# dsc.net
KiCad netlist of a schematic drawn in EAGLE
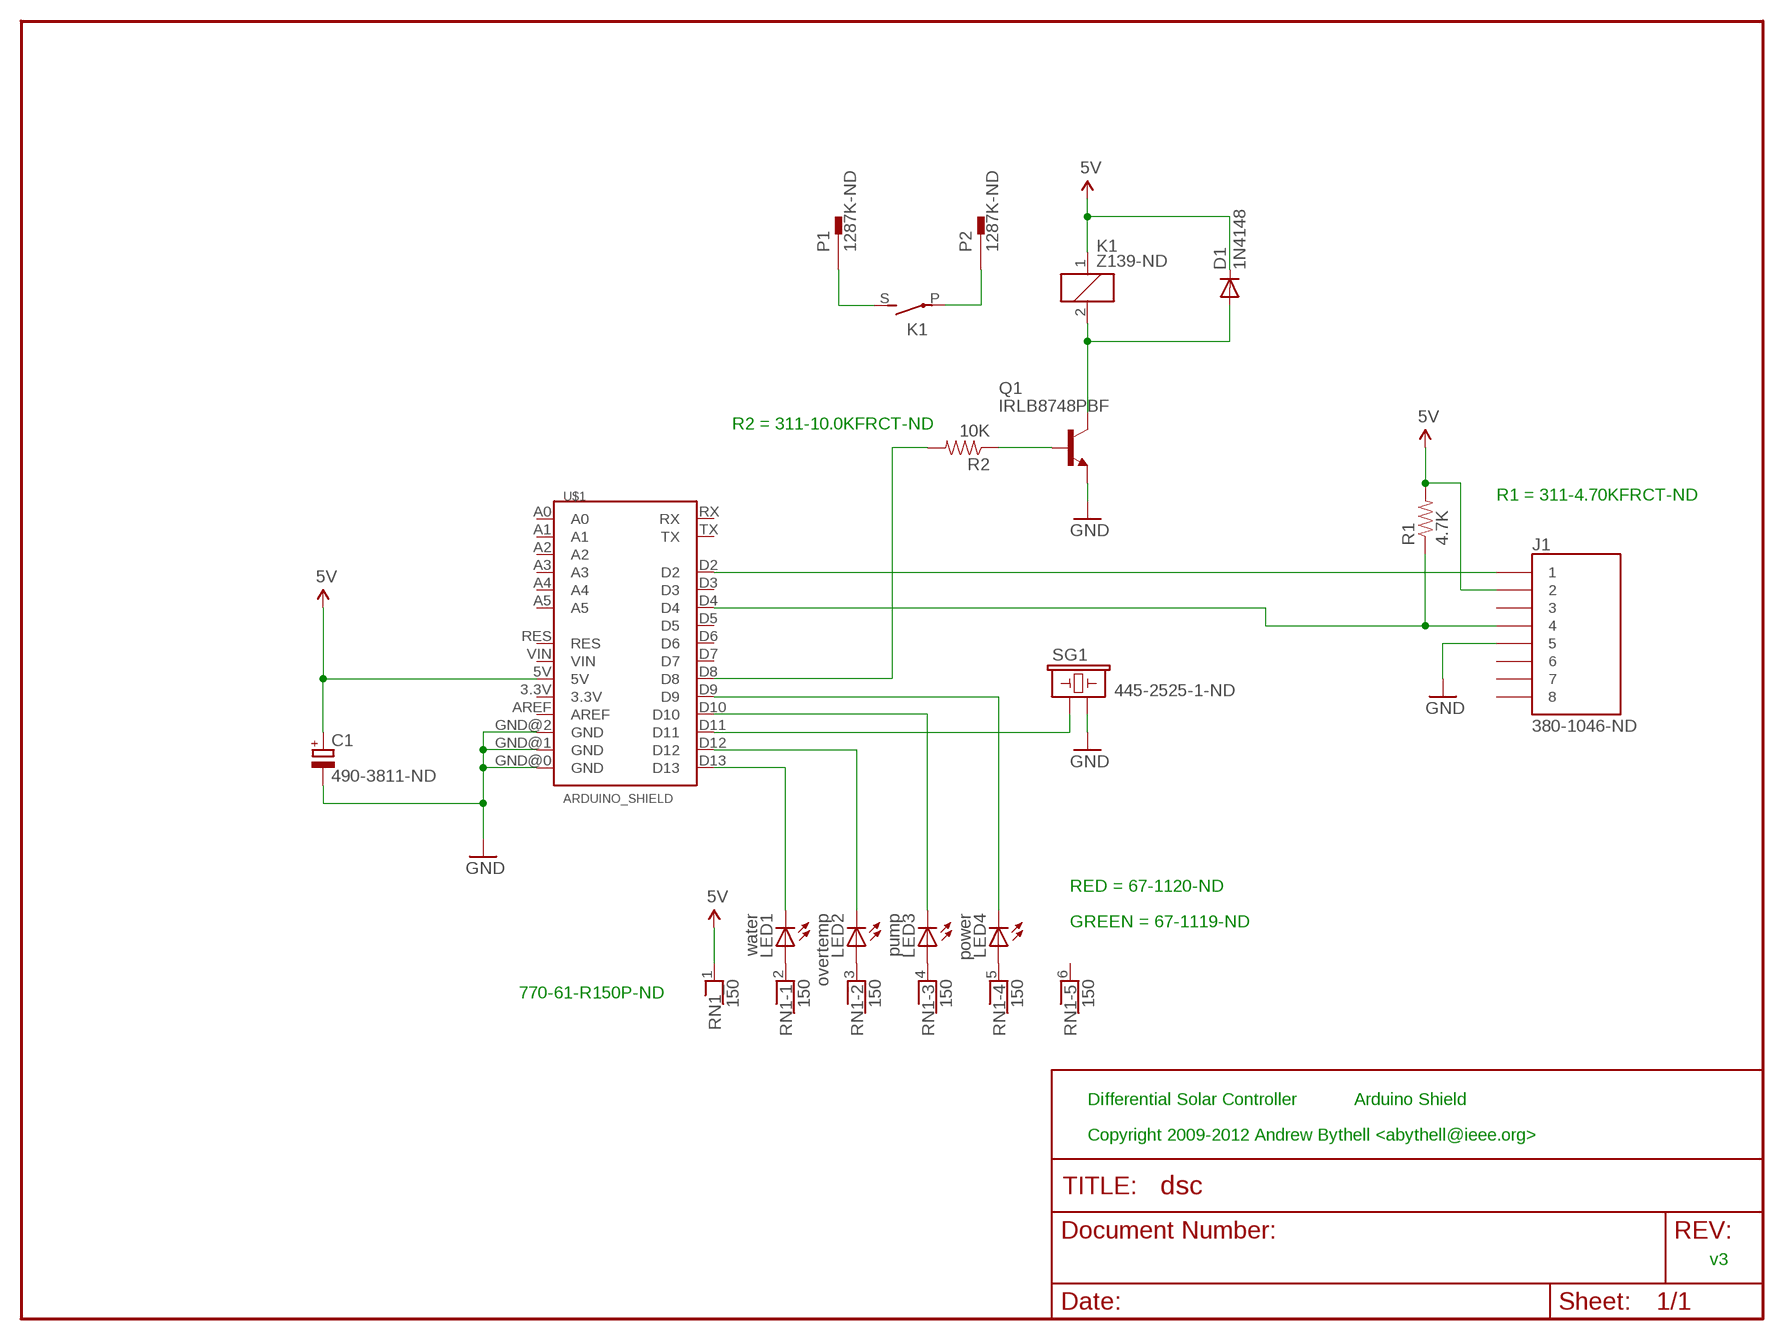
[diagram p0: schematic, sheet 1]

(export (version "E")
  (design (tool "Eeschema 10.0.6"))
  (components
    (comp (ref "C1")
      (value "490-3811-ND")
      (footprint "eagle-import:E3,5-8")
      (libsource (lib "eagle-import") (part "CPOL-EUE3.5-8"))
    )
    (comp (ref "D1")
      (value "1N4148")
      (footprint "eagle-import:DO35-10")
      (libsource (lib "eagle-import") (part "1N4148DO35-10"))
    )
    (comp (ref "J1")
      (value "380-1046-ND")
      (footprint "eagle-import:RJ45-8")
      (libsource (lib "eagle-import") (part "RJ45-8PTH"))
    )
    (comp (ref "K1")
      (value "Z139-ND")
      (footprint "eagle-import:G2RA")
      (libsource (lib "eagle-import") (part "G2RA"))
    )
    (comp (ref "LED1")
      (value "water")
      (footprint "eagle-import:LED5MM")
      (libsource (lib "eagle-import") (part "LED5MM"))
    )
    (comp (ref "LED2")
      (value "overtemp")
      (footprint "eagle-import:LED5MM")
      (libsource (lib "eagle-import") (part "LED5MM"))
    )
    (comp (ref "LED3")
      (value "pump")
      (footprint "eagle-import:LED5MM")
      (libsource (lib "eagle-import") (part "LED5MM"))
    )
    (comp (ref "LED4")
      (value "power")
      (footprint "eagle-import:LED5MM")
      (libsource (lib "eagle-import") (part "LED5MM"))
    )
    (comp (ref "P1")
      (value "1287K-ND")
      (footprint "eagle-import:F061.100")
      (libsource (lib "eagle-import") (part "PIN2F061.100"))
    )
    (comp (ref "P2")
      (value "1287K-ND")
      (footprint "eagle-import:F061.100")
      (libsource (lib "eagle-import") (part "PIN2F061.100"))
    )
    (comp (ref "Q1")
      (value "IRLB8748PBF")
      (footprint "eagle-import:TO18")
      (libsource (lib "eagle-import") (part "2N2222"))
    )
    (comp (ref "R1")
      (value "4.7K")
      (footprint "eagle-import:1206")
      (libsource (lib "eagle-import") (part "RESISTOR1206"))
    )
    (comp (ref "R2")
      (value "10K")
      (footprint "eagle-import:1206")
      (libsource (lib "eagle-import") (part "RESISTOR1206"))
    )
    (comp (ref "RN1")
      (value "150")
      (footprint "eagle-import:RN-6")
      (libsource (lib "eagle-import") (part "RNX5"))
    )
    (comp (ref "SG1")
      (value "445-2525-1-ND")
      (footprint "eagle-import:BUZZER-12MM-AB")
      (libsource (lib "eagle-import") (part "BUZZER"))
    )
    (comp (ref "U$1")
      (value "ARDUINO_SHIELD")
      (footprint "eagle-import:DUEMILANOVE_SHIELD")
      (libsource (lib "eagle-import") (part "ARDUINO_SHIELD"))
    )
  )
  (nets
    (net (code "1") (name "5V") (class "Default")
      (node (ref "C1") (pin "+") (pinfunction "+_+") (pintype "passive"))
      (node (ref "D1") (pin "C") (pinfunction "C_C") (pintype "passive"))
      (node (ref "J1") (pin "2") (pinfunction "2_2") (pintype "bidirectional"))
      (node (ref "K1") (pin "1") (pinfunction "1_1") (pintype "passive"))
      (node (ref "R1") (pin "2") (pinfunction "2_2") (pintype "passive"))
      (node (ref "RN1") (pin "1") (pinfunction "1_1") (pintype "passive"))
      (node (ref "U$1") (pin "5V") (pinfunction "5V_5V") (pintype "bidirectional"))
    )
    (net (code "2") (name "GND") (class "Default")
      (node (ref "C1") (pin "-") (pinfunction "-_-") (pintype "passive"))
      (node (ref "J1") (pin "5") (pinfunction "5_5") (pintype "bidirectional"))
      (node (ref "Q1") (pin "1") (pinfunction "E_1") (pintype "passive"))
      (node (ref "SG1") (pin "-") (pinfunction "2_-") (pintype "passive"))
      (node (ref "U$1") (pin "GND@0") (pinfunction "GND_GND@0") (pintype "bidirectional"))
      (node (ref "U$1") (pin "GND@1") (pinfunction "GND_GND@1") (pintype "bidirectional"))
      (node (ref "U$1") (pin "GND@2") (pinfunction "GND_GND@2") (pintype "bidirectional"))
    )
    (net (code "3") (name "Net-(J1-Pad1)") (class "Default")
      (node (ref "J1") (pin "1") (pinfunction "1_1") (pintype "bidirectional"))
      (node (ref "U$1") (pin "D2") (pinfunction "D2_D2") (pintype "bidirectional"))
    )
    (net (code "4") (name "Net-(J1-Pad4)") (class "Default")
      (node (ref "J1") (pin "4") (pinfunction "4_4") (pintype "bidirectional"))
      (node (ref "R1") (pin "1") (pinfunction "1_1") (pintype "passive"))
      (node (ref "U$1") (pin "D4") (pinfunction "D4_D4") (pintype "bidirectional"))
    )
    (net (code "5") (name "Net-(K1-PadP)") (class "Default")
      (node (ref "K1") (pin "P") (pinfunction "P_P") (pintype "passive"))
      (node (ref "P2") (pin "A1") (pinfunction "1_A1") (pintype "passive"))
      (node (ref "P2") (pin "A2") (pinfunction "1_A2") (pintype "passive"))
    )
    (net (code "6") (name "Net-(K1-PadS)") (class "Default")
      (node (ref "K1") (pin "S") (pinfunction "S_S") (pintype "passive"))
      (node (ref "P1") (pin "A1") (pinfunction "1_A1") (pintype "passive"))
      (node (ref "P1") (pin "A2") (pinfunction "1_A2") (pintype "passive"))
    )
    (net (code "7") (name "Net-(LED1-C)") (class "Default")
      (node (ref "LED1") (pin "K") (pinfunction "C_K") (pintype "passive"))
      (node (ref "U$1") (pin "D13") (pinfunction "D13_D13") (pintype "bidirectional"))
    )
    (net (code "8") (name "Net-(LED2-C)") (class "Default")
      (node (ref "LED2") (pin "K") (pinfunction "C_K") (pintype "passive"))
      (node (ref "U$1") (pin "D12") (pinfunction "D12_D12") (pintype "bidirectional"))
    )
    (net (code "9") (name "Net-(LED3-C)") (class "Default")
      (node (ref "LED3") (pin "K") (pinfunction "C_K") (pintype "passive"))
      (node (ref "U$1") (pin "D10") (pinfunction "D10_D10") (pintype "bidirectional"))
    )
    (net (code "10") (name "Net-(LED4-C)") (class "Default")
      (node (ref "LED4") (pin "K") (pinfunction "C_K") (pintype "passive"))
      (node (ref "U$1") (pin "D9") (pinfunction "D9_D9") (pintype "bidirectional"))
    )
    (net (code "11") (name "Net-(Q1-B)") (class "Default")
      (node (ref "Q1") (pin "2") (pinfunction "B_2") (pintype "passive"))
      (node (ref "R2") (pin "1") (pinfunction "1_1") (pintype "passive"))
    )
    (net (code "12") (name "Net-(Q1-C)") (class "Default")
      (node (ref "D1") (pin "A") (pinfunction "A_A") (pintype "passive"))
      (node (ref "K1") (pin "2") (pinfunction "2_2") (pintype "passive"))
      (node (ref "Q1") (pin "3") (pinfunction "C_3") (pintype "passive"))
    )
    (net (code "13") (name "Net-(R2-Pad2)") (class "Default")
      (node (ref "R2") (pin "2") (pinfunction "2_2") (pintype "passive"))
      (node (ref "U$1") (pin "D8") (pinfunction "D8_D8") (pintype "bidirectional"))
    )
    (net (code "14") (name "Net-(RN1A-1)") (class "Default")
      (node (ref "LED1") (pin "A") (pinfunction "A_A") (pintype "passive"))
      (node (ref "RN1") (pin "2") (pinfunction "1_2") (pintype "passive"))
    )
    (net (code "15") (name "Net-(RN1B-1)") (class "Default")
      (node (ref "LED2") (pin "A") (pinfunction "A_A") (pintype "passive"))
      (node (ref "RN1") (pin "3") (pinfunction "1_3") (pintype "passive"))
    )
    (net (code "16") (name "Net-(RN1C-1)") (class "Default")
      (node (ref "LED3") (pin "A") (pinfunction "A_A") (pintype "passive"))
      (node (ref "RN1") (pin "4") (pinfunction "1_4") (pintype "passive"))
    )
    (net (code "17") (name "Net-(RN1D-1)") (class "Default")
      (node (ref "LED4") (pin "A") (pinfunction "A_A") (pintype "passive"))
      (node (ref "RN1") (pin "5") (pinfunction "1_5") (pintype "passive"))
    )
    (net (code "18") (name "Net-(SG1-1)") (class "Default")
      (node (ref "SG1") (pin "+") (pinfunction "1_+") (pintype "passive"))
      (node (ref "U$1") (pin "D11") (pinfunction "D11_D11") (pintype "bidirectional"))
    )
    (net (code "19") (name "unconnected-(J1-Pad3)") (class "Default")
      (node (ref "J1") (pin "3") (pinfunction "3_3") (pintype "bidirectional"))
    )
    (net (code "20") (name "unconnected-(J1-Pad6)") (class "Default")
      (node (ref "J1") (pin "6") (pinfunction "6_6") (pintype "bidirectional"))
    )
    (net (code "21") (name "unconnected-(J1-Pad7)") (class "Default")
      (node (ref "J1") (pin "7") (pinfunction "7_7") (pintype "bidirectional"))
    )
    (net (code "22") (name "unconnected-(J1-Pad8)") (class "Default")
      (node (ref "J1") (pin "8") (pinfunction "8_8") (pintype "bidirectional"))
    )
    (net (code "23") (name "unconnected-(RN1E-1-Pad6)") (class "Default")
      (node (ref "RN1") (pin "6") (pinfunction "1_6") (pintype "passive"))
    )
    (net (code "24") (name "unconnected-(U$1-Pad3.3V)") (class "Default")
      (node (ref "U$1") (pin "3.3V") (pinfunction "3.3V_3.3V") (pintype "bidirectional"))
    )
    (net (code "25") (name "unconnected-(U$1-PadA0)") (class "Default")
      (node (ref "U$1") (pin "A0") (pinfunction "A0_A0") (pintype "bidirectional"))
    )
    (net (code "26") (name "unconnected-(U$1-PadA1)") (class "Default")
      (node (ref "U$1") (pin "A1") (pinfunction "A1_A1") (pintype "bidirectional"))
    )
    (net (code "27") (name "unconnected-(U$1-PadA2)") (class "Default")
      (node (ref "U$1") (pin "A2") (pinfunction "A2_A2") (pintype "bidirectional"))
    )
    (net (code "28") (name "unconnected-(U$1-PadA3)") (class "Default")
      (node (ref "U$1") (pin "A3") (pinfunction "A3_A3") (pintype "bidirectional"))
    )
    (net (code "29") (name "unconnected-(U$1-PadA4)") (class "Default")
      (node (ref "U$1") (pin "A4") (pinfunction "A4_A4") (pintype "bidirectional"))
    )
    (net (code "30") (name "unconnected-(U$1-PadA5)") (class "Default")
      (node (ref "U$1") (pin "A5") (pinfunction "A5_A5") (pintype "bidirectional"))
    )
    (net (code "31") (name "unconnected-(U$1-PadAREF)") (class "Default")
      (node (ref "U$1") (pin "AREF") (pinfunction "AREF_AREF") (pintype "bidirectional"))
    )
    (net (code "32") (name "unconnected-(U$1-PadD3)") (class "Default")
      (node (ref "U$1") (pin "D3") (pinfunction "D3_D3") (pintype "bidirectional"))
    )
    (net (code "33") (name "unconnected-(U$1-PadD5)") (class "Default")
      (node (ref "U$1") (pin "D5") (pinfunction "D5_D5") (pintype "bidirectional"))
    )
    (net (code "34") (name "unconnected-(U$1-PadD6)") (class "Default")
      (node (ref "U$1") (pin "D6") (pinfunction "D6_D6") (pintype "bidirectional"))
    )
    (net (code "35") (name "unconnected-(U$1-PadD7)") (class "Default")
      (node (ref "U$1") (pin "D7") (pinfunction "D7_D7") (pintype "bidirectional"))
    )
    (net (code "36") (name "unconnected-(U$1-PadRES)") (class "Default")
      (node (ref "U$1") (pin "RES") (pinfunction "RES_RES") (pintype "bidirectional"))
    )
    (net (code "37") (name "unconnected-(U$1-PadRX)") (class "Default")
      (node (ref "U$1") (pin "RX") (pinfunction "RX_RX") (pintype "bidirectional"))
    )
    (net (code "38") (name "unconnected-(U$1-PadTX)") (class "Default")
      (node (ref "U$1") (pin "TX") (pinfunction "TX_TX") (pintype "bidirectional"))
    )
    (net (code "39") (name "unconnected-(U$1-PadVIN)") (class "Default")
      (node (ref "U$1") (pin "VIN") (pinfunction "VIN_VIN") (pintype "bidirectional"))
    )
  )
)
